# 2_mppt_circuits.net
KiCad netlist of a schematic drawn in Altium Designer
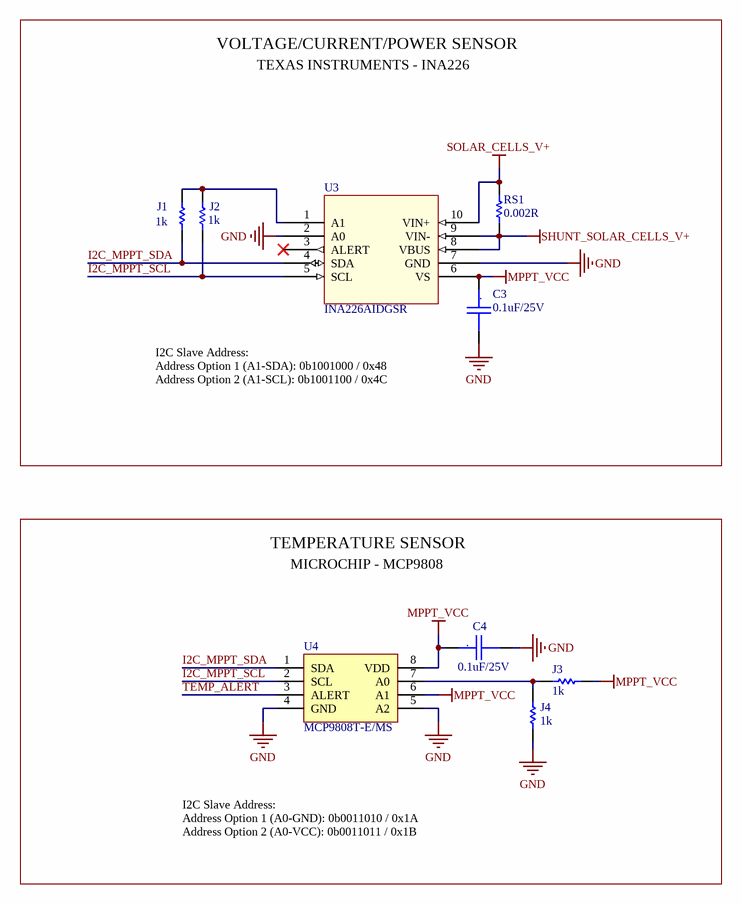
[diagram p0: 2_mppt_circuits.schdoc]

(export (version "E")
  (design (tool "Eeschema 10.0.6"))
  (components
    (comp (ref "C3")
      (value "0.1uF/25V")
      (footprint "CC0805")
      (description "CAP CER 0.1UF 25V 10% X7R 0805")
      (fields (field (name "PARTNUMBER") "CC0805KRX7R8BB104"))
      (libsource (lib "schematics_library_legacy") (part "Cap_Cer_X7R_0.1uF_25V_0805"))
    )
    (comp (ref "C4")
      (value "0.1uF/25V")
      (footprint "CC0805")
      (description "CAP CER 0.1UF 25V 10% X7R 0805")
      (fields (field (name "PARTNUMBER") "CC0805KRX7R8BB104"))
      (libsource (lib "schematics_library_legacy") (part "Cap_Cer_X7R_0.1uF_25V_0805"))
    )
    (comp (ref "J1")
      (value "1k")
      (footprint "0805")
      (description "RES 1.0K OHM 1/8W 1% 0805")
      (fields (field (name "PARTNUMBER") "RC0805FR-071KL"))
      (libsource (lib "schematics_library_legacy") (part "R1.0k_1%_1/8W_0805"))
    )
    (comp (ref "J2")
      (value "1k")
      (footprint "0805")
      (description "RES 1.0K OHM 1/8W 1% 0805")
      (fields (field (name "PARTNUMBER") "RC0805FR-071KL"))
      (libsource (lib "schematics_library_legacy") (part "R1.0k_1%_1/8W_0805"))
    )
    (comp (ref "J3")
      (value "1k")
      (footprint "0805")
      (description "RES 1.0K OHM 1/8W 1% 0805")
      (fields (field (name "PARTNUMBER") "RC0805FR-071KL"))
      (libsource (lib "schematics_library_legacy") (part "R1.0k_1%_1/8W_0805"))
    )
    (comp (ref "J4")
      (value "1k")
      (footprint "0805")
      (description "RES 1.0K OHM 1/8W 1% 0805")
      (fields (field (name "PARTNUMBER") "RC0805FR-071KL"))
      (libsource (lib "schematics_library_legacy") (part "R1.0k_1%_1/8W_0805"))
    )
    (comp (ref "RS1")
      (value "0.002R")
      (footprint "0805")
      (description "Current Sense Resistors - SMD 0.002 ohm 3% 0.5W Current Sense")
      (fields (field (name "PARTNUMBER") "LVT08R0020HER"))
      (libsource (lib "schematics_library_legacy") (part "R0.002R_3%_0.5W_0805"))
    )
    (comp (ref "U3")
      (value "INA226AIDGSR")
      (footprint "DGS10")
      (description "High-Side Measurement, Bi-Directional Current/Power Monitor w/I2C Interface")
      (fields
        (field (name "MANUFACTURER") "Texas Instruments")
        (field (name "GENERIC_PART_NUMBER") "INA226")
        (field (name "COPYRIGHT") "Copyright (C) 2018 Accelerated Designs. All rights reserved")
      )
      (libsource (lib "schematics_library_legacy") (part "INA226AIDGSR"))
    )
    (comp (ref "U4")
      (value "MCP9808T-E/MS")
      (footprint "MSOP-8")
      (libsource (lib "schematics_library_legacy") (part "MCP9808"))
    )
  )
  (nets
    (net (code "1") (name "/I2C_MPPT_SCL") (class "Default")
      (node (ref "J2") (pin "1") (pinfunction "1_1") (pintype "passive"))
      (node (ref "U3") (pin "5") (pinfunction "SCL_5") (pintype "input"))
      (node (ref "U4") (pin "2") (pinfunction "SCL_2") (pintype "passive"))
    )
    (net (code "2") (name "/I2C_MPPT_SDA") (class "Default")
      (node (ref "J1") (pin "1") (pinfunction "1_1") (pintype "passive"))
      (node (ref "U3") (pin "4") (pinfunction "SDA_4") (pintype "bidirectional"))
      (node (ref "U4") (pin "1") (pinfunction "SDA_1") (pintype "passive"))
    )
    (net (code "3") (name "/TEMP_ALERT") (class "Default")
      (node (ref "U4") (pin "3") (pinfunction "ALERT_3") (pintype "passive"))
    )
    (net (code "4") (name "GND") (class "Default")
      (node (ref "C3") (pin "2") (pinfunction "2_2") (pintype "passive"))
      (node (ref "C4") (pin "2") (pinfunction "2_2") (pintype "passive"))
      (node (ref "J4") (pin "1") (pinfunction "1_1") (pintype "passive"))
      (node (ref "U3") (pin "2") (pinfunction "A0_2") (pintype "passive"))
      (node (ref "U3") (pin "7") (pinfunction "GND_7") (pintype "power_in"))
      (node (ref "U4") (pin "4") (pinfunction "GND_4") (pintype "passive"))
      (node (ref "U4") (pin "5") (pinfunction "A2_5") (pintype "passive"))
    )
    (net (code "5") (name "MPPT_VCC") (class "Default")
      (node (ref "C3") (pin "1") (pinfunction "1_1") (pintype "passive"))
      (node (ref "C4") (pin "1") (pinfunction "1_1") (pintype "passive"))
      (node (ref "J3") (pin "1") (pinfunction "1_1") (pintype "passive"))
      (node (ref "U3") (pin "6") (pinfunction "VS_6") (pintype "power_in"))
      (node (ref "U4") (pin "6") (pinfunction "A1_6") (pintype "passive"))
      (node (ref "U4") (pin "8") (pinfunction "VDD_8") (pintype "passive"))
    )
    (net (code "6") (name "Net-(U3-A1)") (class "Default")
      (node (ref "J1") (pin "2") (pinfunction "2_2") (pintype "passive"))
      (node (ref "J2") (pin "2") (pinfunction "2_2") (pintype "passive"))
      (node (ref "U3") (pin "1") (pinfunction "A1_1") (pintype "passive"))
    )
    (net (code "7") (name "Net-(U4-A0)") (class "Default")
      (node (ref "J3") (pin "2") (pinfunction "2_2") (pintype "passive"))
      (node (ref "J4") (pin "2") (pinfunction "2_2") (pintype "passive"))
      (node (ref "U4") (pin "7") (pinfunction "A0_7") (pintype "passive"))
    )
    (net (code "8") (name "SHUNT_SOLAR_CELLS_V+") (class "Default")
      (node (ref "RS1") (pin "1") (pinfunction "1_1") (pintype "passive"))
      (node (ref "U3") (pin "8") (pinfunction "VBUS_8") (pintype "input"))
      (node (ref "U3") (pin "9") (pinfunction "VIN-_9") (pintype "input"))
    )
    (net (code "9") (name "SOLAR_CELLS_V+") (class "Default")
      (node (ref "RS1") (pin "2") (pinfunction "2_2") (pintype "passive"))
      (node (ref "U3") (pin "10") (pinfunction "VIN+_10") (pintype "input"))
    )
    (net (code "10") (name "unconnected-(U3-ALERT-Pad3)") (class "Default")
      (node (ref "U3") (pin "3") (pinfunction "ALERT_3") (pintype "output+no_connect"))
    )
  )
)
